# INPUT_2.net
KiCad netlist of a schematic drawn in EAGLE
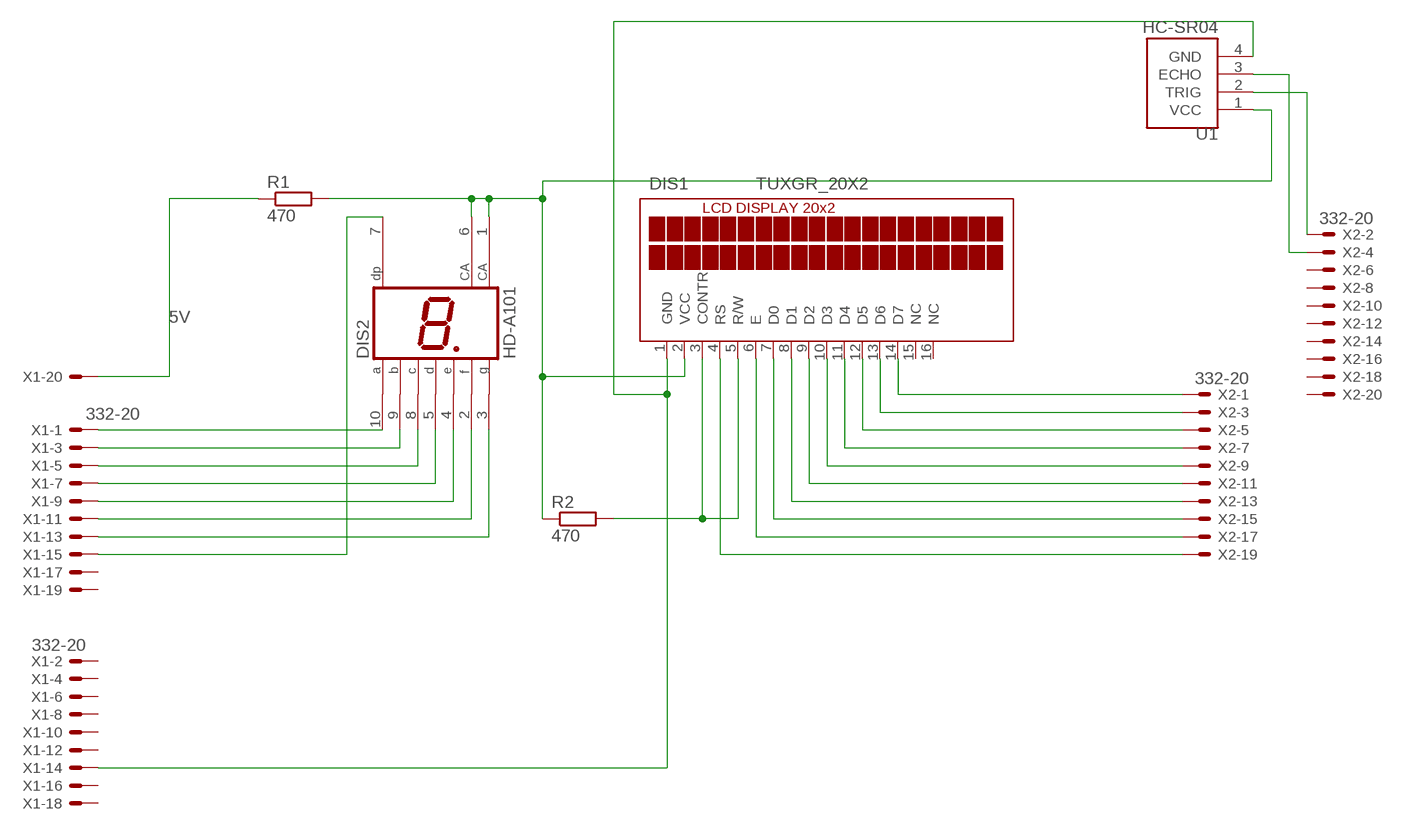
[diagram p0: schematic, sheet 1]

(export (version "E")
  (design (tool "Eeschema 10.0.6"))
  (components
    (comp (ref "DIS1")
      (value "TUXGR_20X2")
      (footprint "eagle-import:TUXGR_20X2")
      (libsource (lib "eagle-import") (part "TUXGR_20X2"))
    )
    (comp (ref "DIS2")
      (value "HD-A101")
      (footprint "eagle-import:HDSP-A")
      (libsource (lib "eagle-import") (part "HD-A101"))
    )
    (comp (ref "R1")
      (value "470")
      (footprint "eagle-import:R0603")
      (libsource (lib "eagle-import") (part "R-EU_R0603"))
    )
    (comp (ref "R2")
      (value "470")
      (footprint "eagle-import:R0603")
      (libsource (lib "eagle-import") (part "R-EU_R0603"))
    )
    (comp (ref "U1")
      (value "HC-SR04")
      (footprint "eagle-import:XCVR_HC-SR04")
      (fields (field (name "MF") "SparkFun Electronics"))
      (libsource (lib "eagle-import") (part "HC-SR04"))
    )
    (comp (ref "X1")
      (value "332-20")
      (footprint "eagle-import:332-20")
      (libsource (lib "eagle-import") (part "332-20"))
    )
    (comp (ref "X2")
      (value "332-20")
      (footprint "eagle-import:332-20")
      (libsource (lib "eagle-import") (part "332-20"))
    )
  )
  (nets
    (net (code "1") (name "/5V") (class "Default")
      (node (ref "R1") (pin "1") (pinfunction "1_1") (pintype "passive"))
      (node (ref "X1") (pin "20") (pinfunction "S_20") (pintype "passive"))
    )
    (net (code "2") (name "Net-(DIS1-CONTR)") (class "Default")
      (node (ref "DIS1") (pin "3") (pinfunction "CONTR_3") (pintype "input"))
      (node (ref "DIS1") (pin "5") (pinfunction "R/W_5") (pintype "input"))
      (node (ref "R2") (pin "2") (pinfunction "2_2") (pintype "passive"))
    )
    (net (code "3") (name "Net-(DIS1-D0)") (class "Default")
      (node (ref "DIS1") (pin "7") (pinfunction "D0_7") (pintype "input"))
      (node (ref "X2") (pin "15") (pinfunction "S_15") (pintype "passive"))
    )
    (net (code "4") (name "Net-(DIS1-D1)") (class "Default")
      (node (ref "DIS1") (pin "8") (pinfunction "D1_8") (pintype "input"))
      (node (ref "X2") (pin "13") (pinfunction "S_13") (pintype "passive"))
    )
    (net (code "5") (name "Net-(DIS1-D2)") (class "Default")
      (node (ref "DIS1") (pin "9") (pinfunction "D2_9") (pintype "input"))
      (node (ref "X2") (pin "11") (pinfunction "S_11") (pintype "passive"))
    )
    (net (code "6") (name "Net-(DIS1-D3)") (class "Default")
      (node (ref "DIS1") (pin "10") (pinfunction "D3_10") (pintype "input"))
      (node (ref "X2") (pin "9") (pinfunction "S_9") (pintype "passive"))
    )
    (net (code "7") (name "Net-(DIS1-D4)") (class "Default")
      (node (ref "DIS1") (pin "11") (pinfunction "D4_11") (pintype "input"))
      (node (ref "X2") (pin "7") (pinfunction "S_7") (pintype "passive"))
    )
    (net (code "8") (name "Net-(DIS1-D5)") (class "Default")
      (node (ref "DIS1") (pin "12") (pinfunction "D5_12") (pintype "input"))
      (node (ref "X2") (pin "5") (pinfunction "S_5") (pintype "passive"))
    )
    (net (code "9") (name "Net-(DIS1-D6)") (class "Default")
      (node (ref "DIS1") (pin "13") (pinfunction "D6_13") (pintype "input"))
      (node (ref "X2") (pin "3") (pinfunction "S_3") (pintype "passive"))
    )
    (net (code "10") (name "Net-(DIS1-D7)") (class "Default")
      (node (ref "DIS1") (pin "14") (pinfunction "D7_14") (pintype "input"))
      (node (ref "X2") (pin "1") (pinfunction "S_1") (pintype "passive"))
    )
    (net (code "11") (name "Net-(DIS1-E)") (class "Default")
      (node (ref "DIS1") (pin "6") (pinfunction "E_6") (pintype "input"))
      (node (ref "X2") (pin "17") (pinfunction "S_17") (pintype "passive"))
    )
    (net (code "12") (name "Net-(DIS1-GND)") (class "Default")
      (node (ref "DIS1") (pin "1") (pinfunction "GND_1") (pintype "power_in"))
      (node (ref "U1") (pin "4") (pinfunction "GND_4") (pintype "power_in"))
      (node (ref "X1") (pin "14") (pinfunction "S_14") (pintype "passive"))
    )
    (net (code "13") (name "Net-(DIS1-RS)") (class "Default")
      (node (ref "DIS1") (pin "4") (pinfunction "RS_4") (pintype "input"))
      (node (ref "X2") (pin "19") (pinfunction "S_19") (pintype "passive"))
    )
    (net (code "14") (name "Net-(DIS1-VCC)") (class "Default")
      (node (ref "DIS1") (pin "2") (pinfunction "VCC_2") (pintype "power_in"))
      (node (ref "DIS2") (pin "1") (pinfunction "CA_1") (pintype "passive"))
      (node (ref "DIS2") (pin "6") (pinfunction "CA_6") (pintype "passive"))
      (node (ref "R1") (pin "2") (pinfunction "2_2") (pintype "passive"))
      (node (ref "R2") (pin "1") (pinfunction "1_1") (pintype "passive"))
      (node (ref "U1") (pin "1") (pinfunction "VCC_1") (pintype "power_in"))
    )
    (net (code "15") (name "Net-(DIS2-A)") (class "Default")
      (node (ref "DIS2") (pin "10") (pinfunction "A_10") (pintype "passive"))
      (node (ref "X1") (pin "1") (pinfunction "S_1") (pintype "passive"))
    )
    (net (code "16") (name "Net-(DIS2-B)") (class "Default")
      (node (ref "DIS2") (pin "9") (pinfunction "B_9") (pintype "passive"))
      (node (ref "X1") (pin "3") (pinfunction "S_3") (pintype "passive"))
    )
    (net (code "17") (name "Net-(DIS2-C)") (class "Default")
      (node (ref "DIS2") (pin "8") (pinfunction "C_8") (pintype "passive"))
      (node (ref "X1") (pin "5") (pinfunction "S_5") (pintype "passive"))
    )
    (net (code "18") (name "Net-(DIS2-D)") (class "Default")
      (node (ref "DIS2") (pin "5") (pinfunction "D_5") (pintype "passive"))
      (node (ref "X1") (pin "7") (pinfunction "S_7") (pintype "passive"))
    )
    (net (code "19") (name "Net-(DIS2-DP)") (class "Default")
      (node (ref "DIS2") (pin "7") (pinfunction "DP_7") (pintype "passive"))
      (node (ref "X1") (pin "15") (pinfunction "S_15") (pintype "passive"))
    )
    (net (code "20") (name "Net-(DIS2-E)") (class "Default")
      (node (ref "DIS2") (pin "4") (pinfunction "E_4") (pintype "passive"))
      (node (ref "X1") (pin "9") (pinfunction "S_9") (pintype "passive"))
    )
    (net (code "21") (name "Net-(DIS2-F)") (class "Default")
      (node (ref "DIS2") (pin "2") (pinfunction "F_2") (pintype "passive"))
      (node (ref "X1") (pin "11") (pinfunction "S_11") (pintype "passive"))
    )
    (net (code "22") (name "Net-(DIS2-G)") (class "Default")
      (node (ref "DIS2") (pin "3") (pinfunction "G_3") (pintype "passive"))
      (node (ref "X1") (pin "13") (pinfunction "S_13") (pintype "passive"))
    )
    (net (code "23") (name "Net-(U1-ECHO)") (class "Default")
      (node (ref "U1") (pin "3") (pinfunction "ECHO_3") (pintype "bidirectional"))
      (node (ref "X2") (pin "4") (pinfunction "S_4") (pintype "passive"))
    )
    (net (code "24") (name "Net-(U1-TRIG)") (class "Default")
      (node (ref "U1") (pin "2") (pinfunction "TRIG_2") (pintype "bidirectional"))
      (node (ref "X2") (pin "2") (pinfunction "S_2") (pintype "passive"))
    )
    (net (code "25") (name "unconnected-(DIS1-NC-Pad15)") (class "Default")
      (node (ref "DIS1") (pin "15") (pinfunction "NC_15") (pintype "no_connect"))
    )
    (net (code "26") (name "unconnected-(DIS1-NC-Pad16)") (class "Default")
      (node (ref "DIS1") (pin "16") (pinfunction "NC_16") (pintype "no_connect"))
    )
    (net (code "27") (name "unconnected-(X1B-S-Pad10)") (class "Default")
      (node (ref "X1") (pin "10") (pinfunction "S_10") (pintype "passive"))
    )
    (net (code "28") (name "unconnected-(X1D-S-Pad12)") (class "Default")
      (node (ref "X1") (pin "12") (pinfunction "S_12") (pintype "passive"))
    )
    (net (code "29") (name "unconnected-(X1H-S-Pad16)") (class "Default")
      (node (ref "X1") (pin "16") (pinfunction "S_16") (pintype "passive"))
    )
    (net (code "30") (name "unconnected-(X1I-S-Pad17)") (class "Default")
      (node (ref "X1") (pin "17") (pinfunction "S_17") (pintype "passive"))
    )
    (net (code "31") (name "unconnected-(X1J-S-Pad18)") (class "Default")
      (node (ref "X1") (pin "18") (pinfunction "S_18") (pintype "passive"))
    )
    (net (code "32") (name "unconnected-(X1K-S-Pad19)") (class "Default")
      (node (ref "X1") (pin "19") (pinfunction "S_19") (pintype "passive"))
    )
    (net (code "33") (name "unconnected-(X1L-S-Pad2)") (class "Default")
      (node (ref "X1") (pin "2") (pinfunction "S_2") (pintype "passive"))
    )
    (net (code "34") (name "unconnected-(X1O-S-Pad4)") (class "Default")
      (node (ref "X1") (pin "4") (pinfunction "S_4") (pintype "passive"))
    )
    (net (code "35") (name "unconnected-(X1Q-S-Pad6)") (class "Default")
      (node (ref "X1") (pin "6") (pinfunction "S_6") (pintype "passive"))
    )
    (net (code "36") (name "unconnected-(X1S-S-Pad8)") (class "Default")
      (node (ref "X1") (pin "8") (pinfunction "S_8") (pintype "passive"))
    )
    (net (code "37") (name "unconnected-(X2B-S-Pad10)") (class "Default")
      (node (ref "X2") (pin "10") (pinfunction "S_10") (pintype "passive"))
    )
    (net (code "38") (name "unconnected-(X2D-S-Pad12)") (class "Default")
      (node (ref "X2") (pin "12") (pinfunction "S_12") (pintype "passive"))
    )
    (net (code "39") (name "unconnected-(X2F-S-Pad14)") (class "Default")
      (node (ref "X2") (pin "14") (pinfunction "S_14") (pintype "passive"))
    )
    (net (code "40") (name "unconnected-(X2H-S-Pad16)") (class "Default")
      (node (ref "X2") (pin "16") (pinfunction "S_16") (pintype "passive"))
    )
    (net (code "41") (name "unconnected-(X2J-S-Pad18)") (class "Default")
      (node (ref "X2") (pin "18") (pinfunction "S_18") (pintype "passive"))
    )
    (net (code "42") (name "unconnected-(X2M-S-Pad20)") (class "Default")
      (node (ref "X2") (pin "20") (pinfunction "S_20") (pintype "passive"))
    )
    (net (code "43") (name "unconnected-(X2Q-S-Pad6)") (class "Default")
      (node (ref "X2") (pin "6") (pinfunction "S_6") (pintype "passive"))
    )
    (net (code "44") (name "unconnected-(X2S-S-Pad8)") (class "Default")
      (node (ref "X2") (pin "8") (pinfunction "S_8") (pintype "passive"))
    )
  )
)
